# LilyPad-Simple-v25.net
KiCad netlist of a schematic drawn in EAGLE
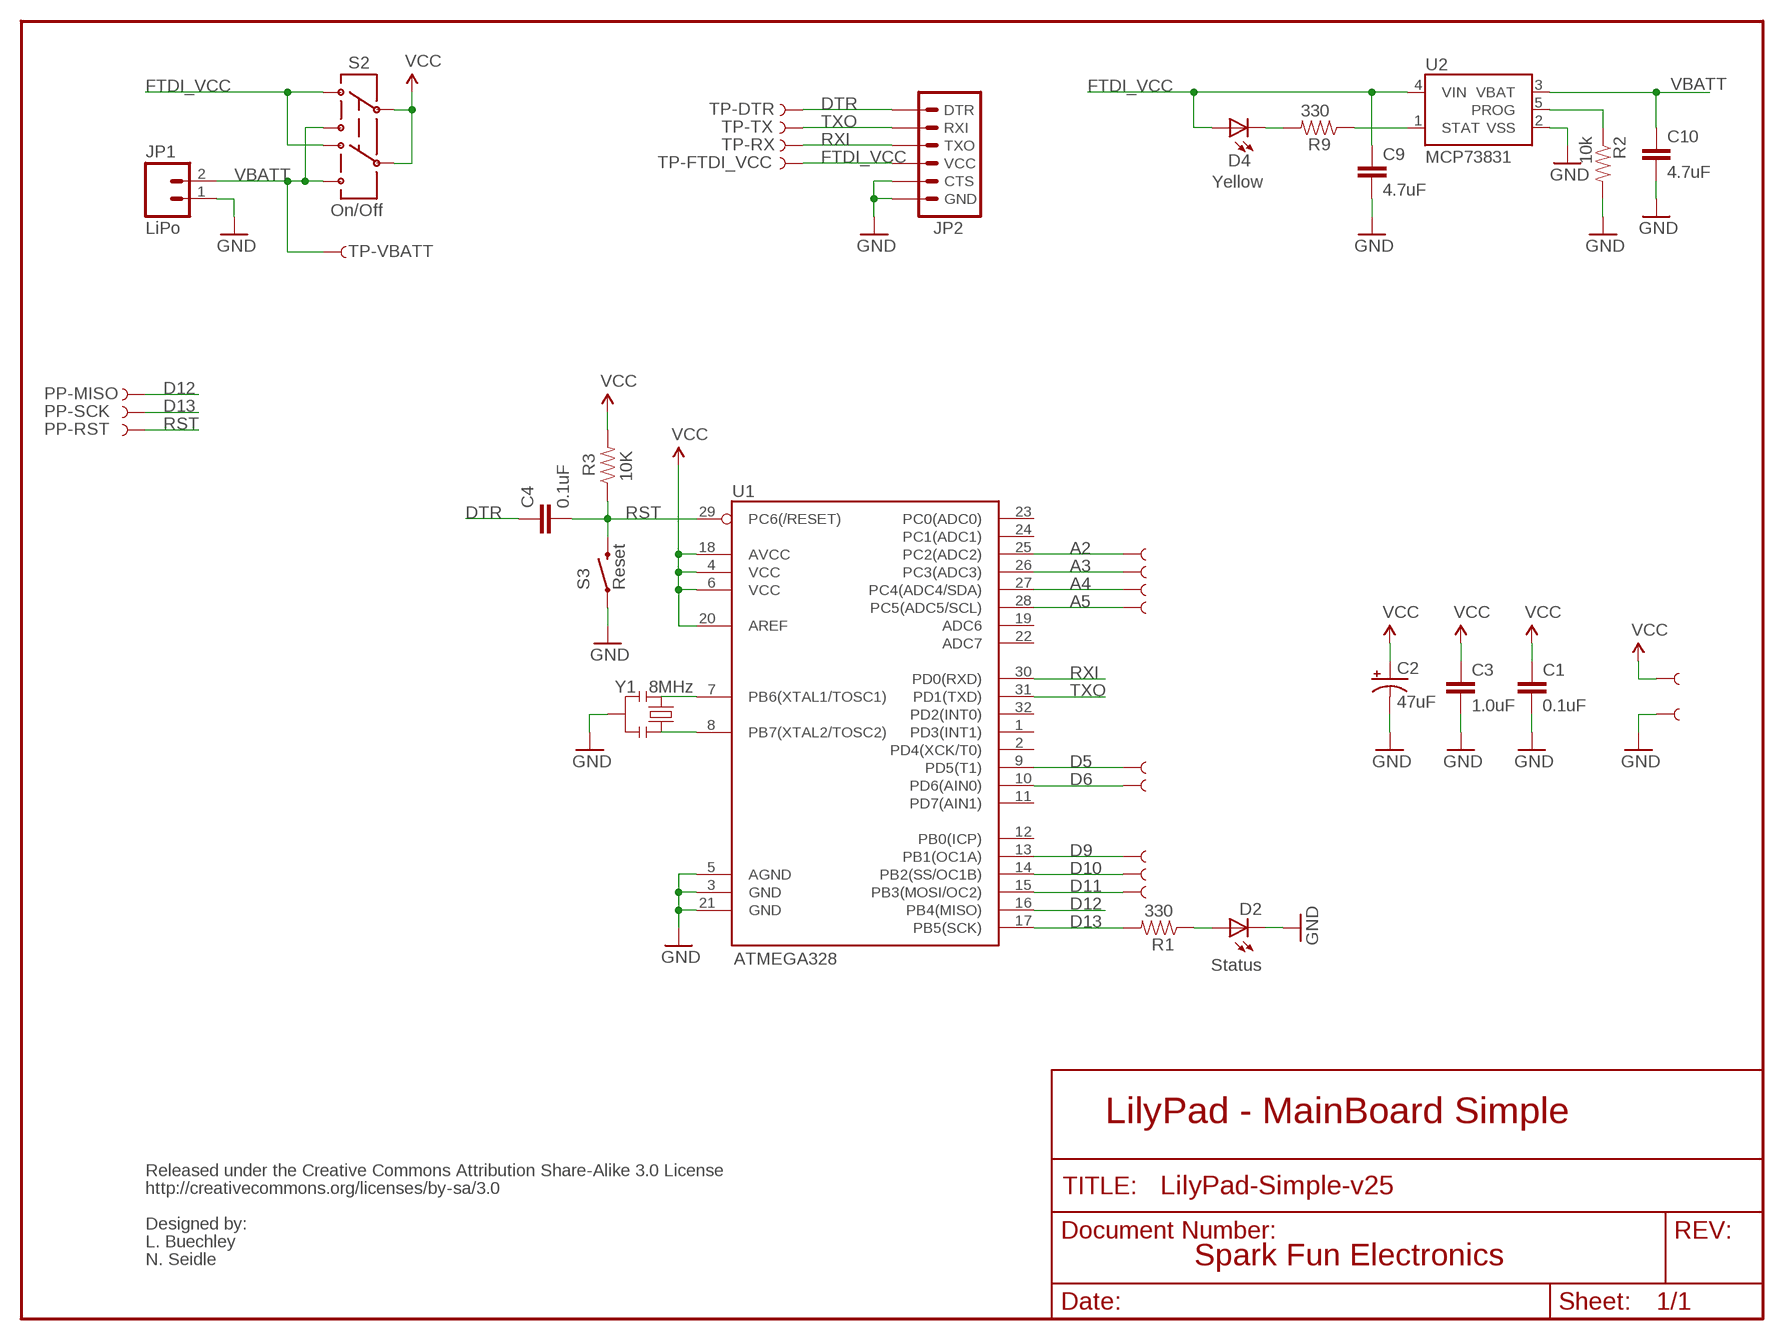
[diagram p0: schematic, sheet 1]

(export (version "E")
  (design (tool "Eeschema 10.0.6"))
  (components
    (comp (ref "A2/16")
      (value "SEWTAP9")
      (footprint "eagle-import:PETAL-LONG-1-2SIDE")
      (libsource (lib "eagle-import") (part "SEWTAP9"))
    )
    (comp (ref "A3/17")
      (value "SEWTAP9")
      (footprint "eagle-import:PETAL-LONG-1-2SIDE")
      (libsource (lib "eagle-import") (part "SEWTAP9"))
    )
    (comp (ref "A4/18")
      (value "SEWTAP9")
      (footprint "eagle-import:PETAL-LONG-1-2SIDE")
      (libsource (lib "eagle-import") (part "SEWTAP9"))
    )
    (comp (ref "A5/19")
      (value "SEWTAP9")
      (footprint "eagle-import:PETAL-LONG-1-2SIDE")
      (libsource (lib "eagle-import") (part "SEWTAP9"))
    )
    (comp (ref "C1")
      (value "0.1uF")
      (footprint "eagle-import:0402-CAP")
      (libsource (lib "eagle-import") (part "CAP0402-CAP"))
    )
    (comp (ref "C2")
      (value "47uF")
      (footprint "eagle-import:EIA3528")
      (libsource (lib "eagle-import") (part "CAP_POL3528"))
    )
    (comp (ref "C3")
      (value "1.0uF")
      (footprint "eagle-import:0402-CAP")
      (libsource (lib "eagle-import") (part "CAP0402-CAP"))
    )
    (comp (ref "C4")
      (value "0.1uF")
      (footprint "eagle-import:0402-CAP")
      (libsource (lib "eagle-import") (part "CAP0402-CAP"))
    )
    (comp (ref "C9")
      (value "4.7uF")
      (footprint "eagle-import:0402-CAP")
      (libsource (lib "eagle-import") (part "CAP0402-CAP"))
    )
    (comp (ref "C10")
      (value "4.7uF")
      (footprint "eagle-import:0402-CAP")
      (libsource (lib "eagle-import") (part "CAP0402-CAP"))
    )
    (comp (ref "D2")
      (value "Status")
      (footprint "eagle-import:LED-0603")
      (libsource (lib "eagle-import") (part "LED0603"))
    )
    (comp (ref "D4")
      (value "Yellow")
      (footprint "eagle-import:LED-0603")
      (libsource (lib "eagle-import") (part "LED0603"))
    )
    (comp (ref "JP1")
      (value "LiPo")
      (footprint "eagle-import:JST-2-SMD")
      (libsource (lib "eagle-import") (part "M02-JST-2MM-SMT"))
    )
    (comp (ref "JP2")
      (value "ARDUINO_SERIAL_PROGRAMSMD")
      (footprint "eagle-import:1X06-SMD")
      (libsource (lib "eagle-import") (part "ARDUINO_SERIAL_PROGRAMSMD"))
    )
    (comp (ref "PP-MISO")
      (value "TEST-POINT3X5")
      (footprint "eagle-import:PAD.03X.05")
      (libsource (lib "eagle-import") (part "TEST-POINT3X5"))
    )
    (comp (ref "PP-RST")
      (value "TEST-POINT3X5")
      (footprint "eagle-import:PAD.03X.05")
      (libsource (lib "eagle-import") (part "TEST-POINT3X5"))
    )
    (comp (ref "PP-SCK")
      (value "TEST-POINT3X5")
      (footprint "eagle-import:PAD.03X.05")
      (libsource (lib "eagle-import") (part "TEST-POINT3X5"))
    )
    (comp (ref "R1")
      (value "330")
      (footprint "eagle-import:0402-RES")
      (libsource (lib "eagle-import") (part "RESISTOR0402-RES"))
    )
    (comp (ref "R2")
      (value "10k")
      (footprint "eagle-import:0402-RES")
      (libsource (lib "eagle-import") (part "RESISTOR0402-RES"))
    )
    (comp (ref "R3")
      (value "10K")
      (footprint "eagle-import:0402-RES")
      (libsource (lib "eagle-import") (part "RESISTOR0402-RES"))
    )
    (comp (ref "R9")
      (value "330")
      (footprint "eagle-import:0402-RES")
      (libsource (lib "eagle-import") (part "RESISTOR0402-RES"))
    )
    (comp (ref "S2")
      (value "On/Off")
      (footprint "eagle-import:AYZ0202")
      (libsource (lib "eagle-import") (part "AYZ0202"))
    )
    (comp (ref "S3")
      (value "Reset")
      (footprint "eagle-import:TACTILE_SWITCH_SMD")
      (libsource (lib "eagle-import") (part "SWITCH-MOMENTARY-2SMD"))
    )
    (comp (ref "TP-DTR")
      (value "TEST-POINT3X5")
      (footprint "eagle-import:PAD.03X.05")
      (libsource (lib "eagle-import") (part "TEST-POINT3X5"))
    )
    (comp (ref "TP-FTDI_VCC")
      (value "TEST-POINT3X5")
      (footprint "eagle-import:PAD.03X.05")
      (libsource (lib "eagle-import") (part "TEST-POINT3X5"))
    )
    (comp (ref "TP-RX")
      (value "TEST-POINT3X5")
      (footprint "eagle-import:PAD.03X.05")
      (libsource (lib "eagle-import") (part "TEST-POINT3X5"))
    )
    (comp (ref "TP-TX")
      (value "TEST-POINT3X5")
      (footprint "eagle-import:PAD.03X.05")
      (libsource (lib "eagle-import") (part "TEST-POINT3X5"))
    )
    (comp (ref "TP-VBATT")
      (value "TEST-POINT3X5")
      (footprint "eagle-import:PAD.03X.05")
      (libsource (lib "eagle-import") (part "TEST-POINT3X5"))
    )
    (comp (ref "U$4")
      (value "SEWTAP9")
      (footprint "eagle-import:PETAL-LONG-1-2SIDE")
      (libsource (lib "eagle-import") (part "SEWTAP9"))
    )
    (comp (ref "U$35")
      (value "SEWTAP9")
      (footprint "eagle-import:PETAL-LONG-1-2SIDE")
      (libsource (lib "eagle-import") (part "SEWTAP9"))
    )
    (comp (ref "U$37")
      (value "SEWTAP9")
      (footprint "eagle-import:PETAL-LONG-1-2SIDE")
      (libsource (lib "eagle-import") (part "SEWTAP9"))
    )
    (comp (ref "U$39")
      (value "SEWTAP9")
      (footprint "eagle-import:PETAL-LONG-1-2SIDE")
      (libsource (lib "eagle-import") (part "SEWTAP9"))
    )
    (comp (ref "U$41")
      (value "SEWTAP9")
      (footprint "eagle-import:PETAL-LONG-1-2SIDE")
      (libsource (lib "eagle-import") (part "SEWTAP9"))
    )
    (comp (ref "U$43")
      (value "SEWTAP9")
      (footprint "eagle-import:PETAL-LONG-1-2SIDE")
      (libsource (lib "eagle-import") (part "SEWTAP9"))
    )
    (comp (ref "U$45")
      (value "SEWTAP9")
      (footprint "eagle-import:PETAL-LONG-1-2SIDE")
      (libsource (lib "eagle-import") (part "SEWTAP9"))
    )
    (comp (ref "U1")
      (value "ATMEGA328")
      (footprint "eagle-import:TQFP32-08")
      (libsource (lib "eagle-import") (part "ATMEGA168"))
    )
    (comp (ref "U2")
      (value "MCP73831")
      (footprint "eagle-import:SOT23-5")
      (libsource (lib "eagle-import") (part "MCP73831"))
    )
    (comp (ref "Y1")
      (value "8MHz")
      (footprint "eagle-import:RESONATOR-SMD")
      (libsource (lib "eagle-import") (part "RESONATORSMD"))
    )
  )
  (nets
    (net (code "1") (name "/A2") (class "Default")
      (node (ref "A2/16") (pin "1") (pinfunction "1_1") (pintype "bidirectional"))
      (node (ref "U1") (pin "25") (pinfunction "PC2(ADC2)_25") (pintype "bidirectional"))
    )
    (net (code "2") (name "/A3") (class "Default")
      (node (ref "A3/17") (pin "1") (pinfunction "1_1") (pintype "bidirectional"))
      (node (ref "U1") (pin "26") (pinfunction "PC3(ADC3)_26") (pintype "bidirectional"))
    )
    (net (code "3") (name "/A4") (class "Default")
      (node (ref "A4/18") (pin "1") (pinfunction "1_1") (pintype "bidirectional"))
      (node (ref "U1") (pin "27") (pinfunction "PC4(ADC4/SDA)_27") (pintype "bidirectional"))
    )
    (net (code "4") (name "/A5") (class "Default")
      (node (ref "A5/19") (pin "1") (pinfunction "1_1") (pintype "bidirectional"))
      (node (ref "U1") (pin "28") (pinfunction "PC5(ADC5/SCL)_28") (pintype "bidirectional"))
    )
    (net (code "5") (name "/D5") (class "Default")
      (node (ref "U$41") (pin "1") (pinfunction "1_1") (pintype "bidirectional"))
      (node (ref "U1") (pin "9") (pinfunction "PD5(T1)_9") (pintype "bidirectional"))
    )
    (net (code "6") (name "/D6") (class "Default")
      (node (ref "U$35") (pin "1") (pinfunction "1_1") (pintype "bidirectional"))
      (node (ref "U1") (pin "10") (pinfunction "PD6(AIN0)_10") (pintype "bidirectional"))
    )
    (net (code "7") (name "/D9") (class "Default")
      (node (ref "U$37") (pin "1") (pinfunction "1_1") (pintype "bidirectional"))
      (node (ref "U1") (pin "13") (pinfunction "PB1(OC1A)_13") (pintype "bidirectional"))
    )
    (net (code "8") (name "/D10") (class "Default")
      (node (ref "U$39") (pin "1") (pinfunction "1_1") (pintype "bidirectional"))
      (node (ref "U1") (pin "14") (pinfunction "PB2(SS/OC1B)_14") (pintype "bidirectional"))
    )
    (net (code "9") (name "/D11") (class "Default")
      (node (ref "U$4") (pin "1") (pinfunction "1_1") (pintype "bidirectional"))
      (node (ref "U1") (pin "15") (pinfunction "PB3(MOSI/OC2)_15") (pintype "bidirectional"))
    )
    (net (code "10") (name "/D12") (class "Default")
      (node (ref "PP-MISO") (pin "P$1") (pinfunction "1_P$1") (pintype "bidirectional"))
      (node (ref "U1") (pin "16") (pinfunction "PB4(MISO)_16") (pintype "bidirectional"))
    )
    (net (code "11") (name "/D13") (class "Default")
      (node (ref "PP-SCK") (pin "P$1") (pinfunction "1_P$1") (pintype "bidirectional"))
      (node (ref "R1") (pin "2") (pinfunction "2_2") (pintype "passive"))
      (node (ref "U1") (pin "17") (pinfunction "PB5(SCK)_17") (pintype "bidirectional"))
    )
    (net (code "12") (name "/DTR") (class "Default")
      (node (ref "C4") (pin "1") (pinfunction "1_1") (pintype "passive"))
      (node (ref "JP2") (pin "1") (pinfunction "DTR_1") (pintype "passive"))
      (node (ref "TP-DTR") (pin "P$1") (pinfunction "1_P$1") (pintype "bidirectional"))
    )
    (net (code "13") (name "/FTDI_VCC") (class "Default")
      (node (ref "C9") (pin "1") (pinfunction "1_1") (pintype "passive"))
      (node (ref "D4") (pin "A") (pinfunction "A_A") (pintype "passive"))
      (node (ref "JP2") (pin "4") (pinfunction "VCC_4") (pintype "passive"))
      (node (ref "S2") (pin "3") (pinfunction "1_3") (pintype "bidirectional"))
      (node (ref "S2") (pin "6") (pinfunction "4_6") (pintype "bidirectional"))
      (node (ref "TP-FTDI_VCC") (pin "P$1") (pinfunction "1_P$1") (pintype "bidirectional"))
      (node (ref "U2") (pin "4") (pinfunction "VIN_4") (pintype "power_in"))
    )
    (net (code "14") (name "/RST") (class "Default")
      (node (ref "C4") (pin "2") (pinfunction "2_2") (pintype "passive"))
      (node (ref "PP-RST") (pin "P$1") (pinfunction "1_P$1") (pintype "bidirectional"))
      (node (ref "R3") (pin "1") (pinfunction "1_1") (pintype "passive"))
      (node (ref "S3") (pin "3") (pinfunction "2_3") (pintype "passive"))
      (node (ref "U1") (pin "29") (pinfunction "PC6(/RESET)_29") (pintype "bidirectional"))
    )
    (net (code "15") (name "/RXI") (class "Default")
      (node (ref "JP2") (pin "3") (pinfunction "TXO_3") (pintype "passive"))
      (node (ref "TP-RX") (pin "P$1") (pinfunction "1_P$1") (pintype "bidirectional"))
      (node (ref "U1") (pin "30") (pinfunction "PD0(RXD)_30") (pintype "bidirectional"))
    )
    (net (code "16") (name "/TXO") (class "Default")
      (node (ref "JP2") (pin "2") (pinfunction "RXI_2") (pintype "passive"))
      (node (ref "TP-TX") (pin "P$1") (pinfunction "1_P$1") (pintype "bidirectional"))
      (node (ref "U1") (pin "31") (pinfunction "PD1(TXD)_31") (pintype "bidirectional"))
    )
    (net (code "17") (name "/VBATT") (class "Default")
      (node (ref "C10") (pin "1") (pinfunction "1_1") (pintype "passive"))
      (node (ref "JP1") (pin "2") (pinfunction "2_2") (pintype "passive"))
      (node (ref "S2") (pin "1") (pinfunction "3_1") (pintype "bidirectional"))
      (node (ref "S2") (pin "4") (pinfunction "6_4") (pintype "bidirectional"))
      (node (ref "TP-VBATT") (pin "P$1") (pinfunction "1_P$1") (pintype "bidirectional"))
      (node (ref "U2") (pin "3") (pinfunction "VBAT_3") (pintype "power_in"))
    )
    (net (code "18") (name "GND") (class "Default")
      (node (ref "C1") (pin "2") (pinfunction "2_2") (pintype "passive"))
      (node (ref "C10") (pin "2") (pinfunction "2_2") (pintype "passive"))
      (node (ref "C2") (pin "C") (pinfunction "-_C") (pintype "passive"))
      (node (ref "C3") (pin "2") (pinfunction "2_2") (pintype "passive"))
      (node (ref "C9") (pin "2") (pinfunction "2_2") (pintype "passive"))
      (node (ref "D2") (pin "C") (pinfunction "C_C") (pintype "passive"))
      (node (ref "JP1") (pin "1") (pinfunction "1_1") (pintype "passive"))
      (node (ref "JP2") (pin "5") (pinfunction "CTS_5") (pintype "passive"))
      (node (ref "JP2") (pin "6") (pinfunction "GND_6") (pintype "passive"))
      (node (ref "R2") (pin "2") (pinfunction "2_2") (pintype "passive"))
      (node (ref "S3") (pin "1") (pinfunction "1_1") (pintype "passive"))
      (node (ref "U$43") (pin "1") (pinfunction "1_1") (pintype "bidirectional"))
      (node (ref "U1") (pin "21") (pinfunction "GND_21") (pintype "bidirectional"))
      (node (ref "U1") (pin "3") (pinfunction "GND_3") (pintype "bidirectional"))
      (node (ref "U1") (pin "5") (pinfunction "AGND_5") (pintype "bidirectional"))
      (node (ref "U2") (pin "2") (pinfunction "VSS_2") (pintype "power_in"))
      (node (ref "Y1") (pin "2") (pinfunction "2_2") (pintype "passive"))
    )
    (net (code "19") (name "Net-(D2-PadA)") (class "Default")
      (node (ref "D2") (pin "A") (pinfunction "A_A") (pintype "passive"))
      (node (ref "R1") (pin "1") (pinfunction "1_1") (pintype "passive"))
    )
    (net (code "20") (name "Net-(D4-PadC)") (class "Default")
      (node (ref "D4") (pin "C") (pinfunction "C_C") (pintype "passive"))
      (node (ref "R9") (pin "2") (pinfunction "2_2") (pintype "passive"))
    )
    (net (code "21") (name "Net-(U1-PB6(XTAL1{slash}TOSC1))") (class "Default")
      (node (ref "U1") (pin "7") (pinfunction "PB6(XTAL1/TOSC1)_7") (pintype "bidirectional"))
      (node (ref "Y1") (pin "1") (pinfunction "1_1") (pintype "passive"))
    )
    (net (code "22") (name "Net-(U1-PB7(XTAL2{slash}TOSC2))") (class "Default")
      (node (ref "U1") (pin "8") (pinfunction "PB7(XTAL2/TOSC2)_8") (pintype "bidirectional"))
      (node (ref "Y1") (pin "3") (pinfunction "3_3") (pintype "passive"))
    )
    (net (code "23") (name "Net-(U2-PROG)") (class "Default")
      (node (ref "R2") (pin "1") (pinfunction "1_1") (pintype "passive"))
      (node (ref "U2") (pin "5") (pinfunction "PROG_5") (pintype "input"))
    )
    (net (code "24") (name "Net-(U2-STAT)") (class "Default")
      (node (ref "R9") (pin "1") (pinfunction "1_1") (pintype "passive"))
      (node (ref "U2") (pin "1") (pinfunction "STAT_1") (pintype "output"))
    )
    (net (code "25") (name "VCC") (class "Default")
      (node (ref "C1") (pin "1") (pinfunction "1_1") (pintype "passive"))
      (node (ref "C2") (pin "A") (pinfunction "+_A") (pintype "passive"))
      (node (ref "C3") (pin "1") (pinfunction "1_1") (pintype "passive"))
      (node (ref "R3") (pin "2") (pinfunction "2_2") (pintype "passive"))
      (node (ref "S2") (pin "2") (pinfunction "2_2") (pintype "bidirectional"))
      (node (ref "S2") (pin "5") (pinfunction "5_5") (pintype "bidirectional"))
      (node (ref "U$45") (pin "1") (pinfunction "1_1") (pintype "bidirectional"))
      (node (ref "U1") (pin "18") (pinfunction "AVCC_18") (pintype "bidirectional"))
      (node (ref "U1") (pin "20") (pinfunction "AREF_20") (pintype "bidirectional"))
      (node (ref "U1") (pin "4") (pinfunction "VCC_4") (pintype "bidirectional"))
      (node (ref "U1") (pin "6") (pinfunction "VCC_6") (pintype "bidirectional"))
    )
    (net (code "26") (name "unconnected-(U1-ADC6-Pad19)") (class "Default")
      (node (ref "U1") (pin "19") (pinfunction "ADC6_19") (pintype "bidirectional"))
    )
    (net (code "27") (name "unconnected-(U1-ADC7-Pad22)") (class "Default")
      (node (ref "U1") (pin "22") (pinfunction "ADC7_22") (pintype "bidirectional"))
    )
    (net (code "28") (name "unconnected-(U1-PB0(ICP)-Pad12)") (class "Default")
      (node (ref "U1") (pin "12") (pinfunction "PB0(ICP)_12") (pintype "bidirectional"))
    )
    (net (code "29") (name "unconnected-(U1-PC0(ADC0)-Pad23)") (class "Default")
      (node (ref "U1") (pin "23") (pinfunction "PC0(ADC0)_23") (pintype "bidirectional"))
    )
    (net (code "30") (name "unconnected-(U1-PC1(ADC1)-Pad24)") (class "Default")
      (node (ref "U1") (pin "24") (pinfunction "PC1(ADC1)_24") (pintype "bidirectional"))
    )
    (net (code "31") (name "unconnected-(U1-PD2(INT0)-Pad32)") (class "Default")
      (node (ref "U1") (pin "32") (pinfunction "PD2(INT0)_32") (pintype "bidirectional"))
    )
    (net (code "32") (name "unconnected-(U1-PD3(INT1)-Pad1)") (class "Default")
      (node (ref "U1") (pin "1") (pinfunction "PD3(INT1)_1") (pintype "bidirectional"))
    )
    (net (code "33") (name "unconnected-(U1-PD4(XCK{slash}T0)-Pad2)") (class "Default")
      (node (ref "U1") (pin "2") (pinfunction "PD4(XCK/T0)_2") (pintype "bidirectional"))
    )
    (net (code "34") (name "unconnected-(U1-PD7(AIN1)-Pad11)") (class "Default")
      (node (ref "U1") (pin "11") (pinfunction "PD7(AIN1)_11") (pintype "bidirectional"))
    )
  )
)
